# spindleControl.net
KiCad netlist of a schematic drawn in EAGLE
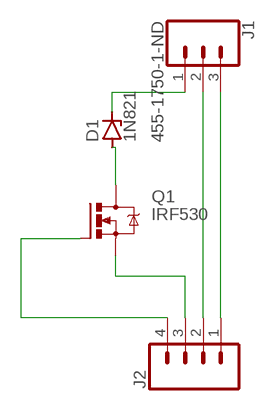
[diagram p0: schematic, sheet 1]

(export (version "E")
  (design (tool "Eeschema 10.0.6"))
  (components
    (comp (ref "D1")
      (value "1N821")
      (footprint "eagle-import:DO35Z10")
      (libsource (lib "eagle-import") (part "1N821"))
    )
    (comp (ref "J1")
      (value "455-1750-1-ND")
      (footprint "eagle-import:1X03")
      (libsource (lib "eagle-import") (part "CONN_03"))
    )
    (comp (ref "J2")
      (value "CONN_04PTH")
      (footprint "eagle-import:1X04")
      (libsource (lib "eagle-import") (part "CONN_04PTH"))
    )
    (comp (ref "Q1")
      (value "IRF530")
      (footprint "eagle-import:TO220BV")
      (libsource (lib "eagle-import") (part "IRF530"))
    )
  )
  (nets
    (net (code "1") (name "Net-(D1-PadA)") (class "Default")
      (node (ref "D1") (pin "A") (pinfunction "A_A") (pintype "passive"))
      (node (ref "Q1") (pin "D") (pinfunction "D_D") (pintype "passive"))
    )
    (net (code "2") (name "Net-(D1-PadC)") (class "Default")
      (node (ref "D1") (pin "C") (pinfunction "C_C") (pintype "passive"))
      (node (ref "J1") (pin "1") (pinfunction "1_1") (pintype "passive"))
    )
    (net (code "3") (name "Net-(J1-Pad2)") (class "Default")
      (node (ref "J1") (pin "2") (pinfunction "2_2") (pintype "passive"))
      (node (ref "J2") (pin "2") (pinfunction "2_2") (pintype "passive"))
    )
    (net (code "4") (name "Net-(J1-Pad3)") (class "Default")
      (node (ref "J1") (pin "3") (pinfunction "3_3") (pintype "passive"))
      (node (ref "J2") (pin "1") (pinfunction "1_1") (pintype "passive"))
    )
    (net (code "5") (name "Net-(J2-Pad3)") (class "Default")
      (node (ref "J2") (pin "3") (pinfunction "3_3") (pintype "passive"))
      (node (ref "Q1") (pin "S") (pinfunction "S_S") (pintype "passive"))
    )
    (net (code "6") (name "Net-(J2-Pad4)") (class "Default")
      (node (ref "J2") (pin "4") (pinfunction "4_4") (pintype "passive"))
      (node (ref "Q1") (pin "G") (pinfunction "G_G") (pintype "passive"))
    )
  )
)
